# VFD-IV-26-5x7.net
KiCad netlist of a schematic drawn in EAGLE
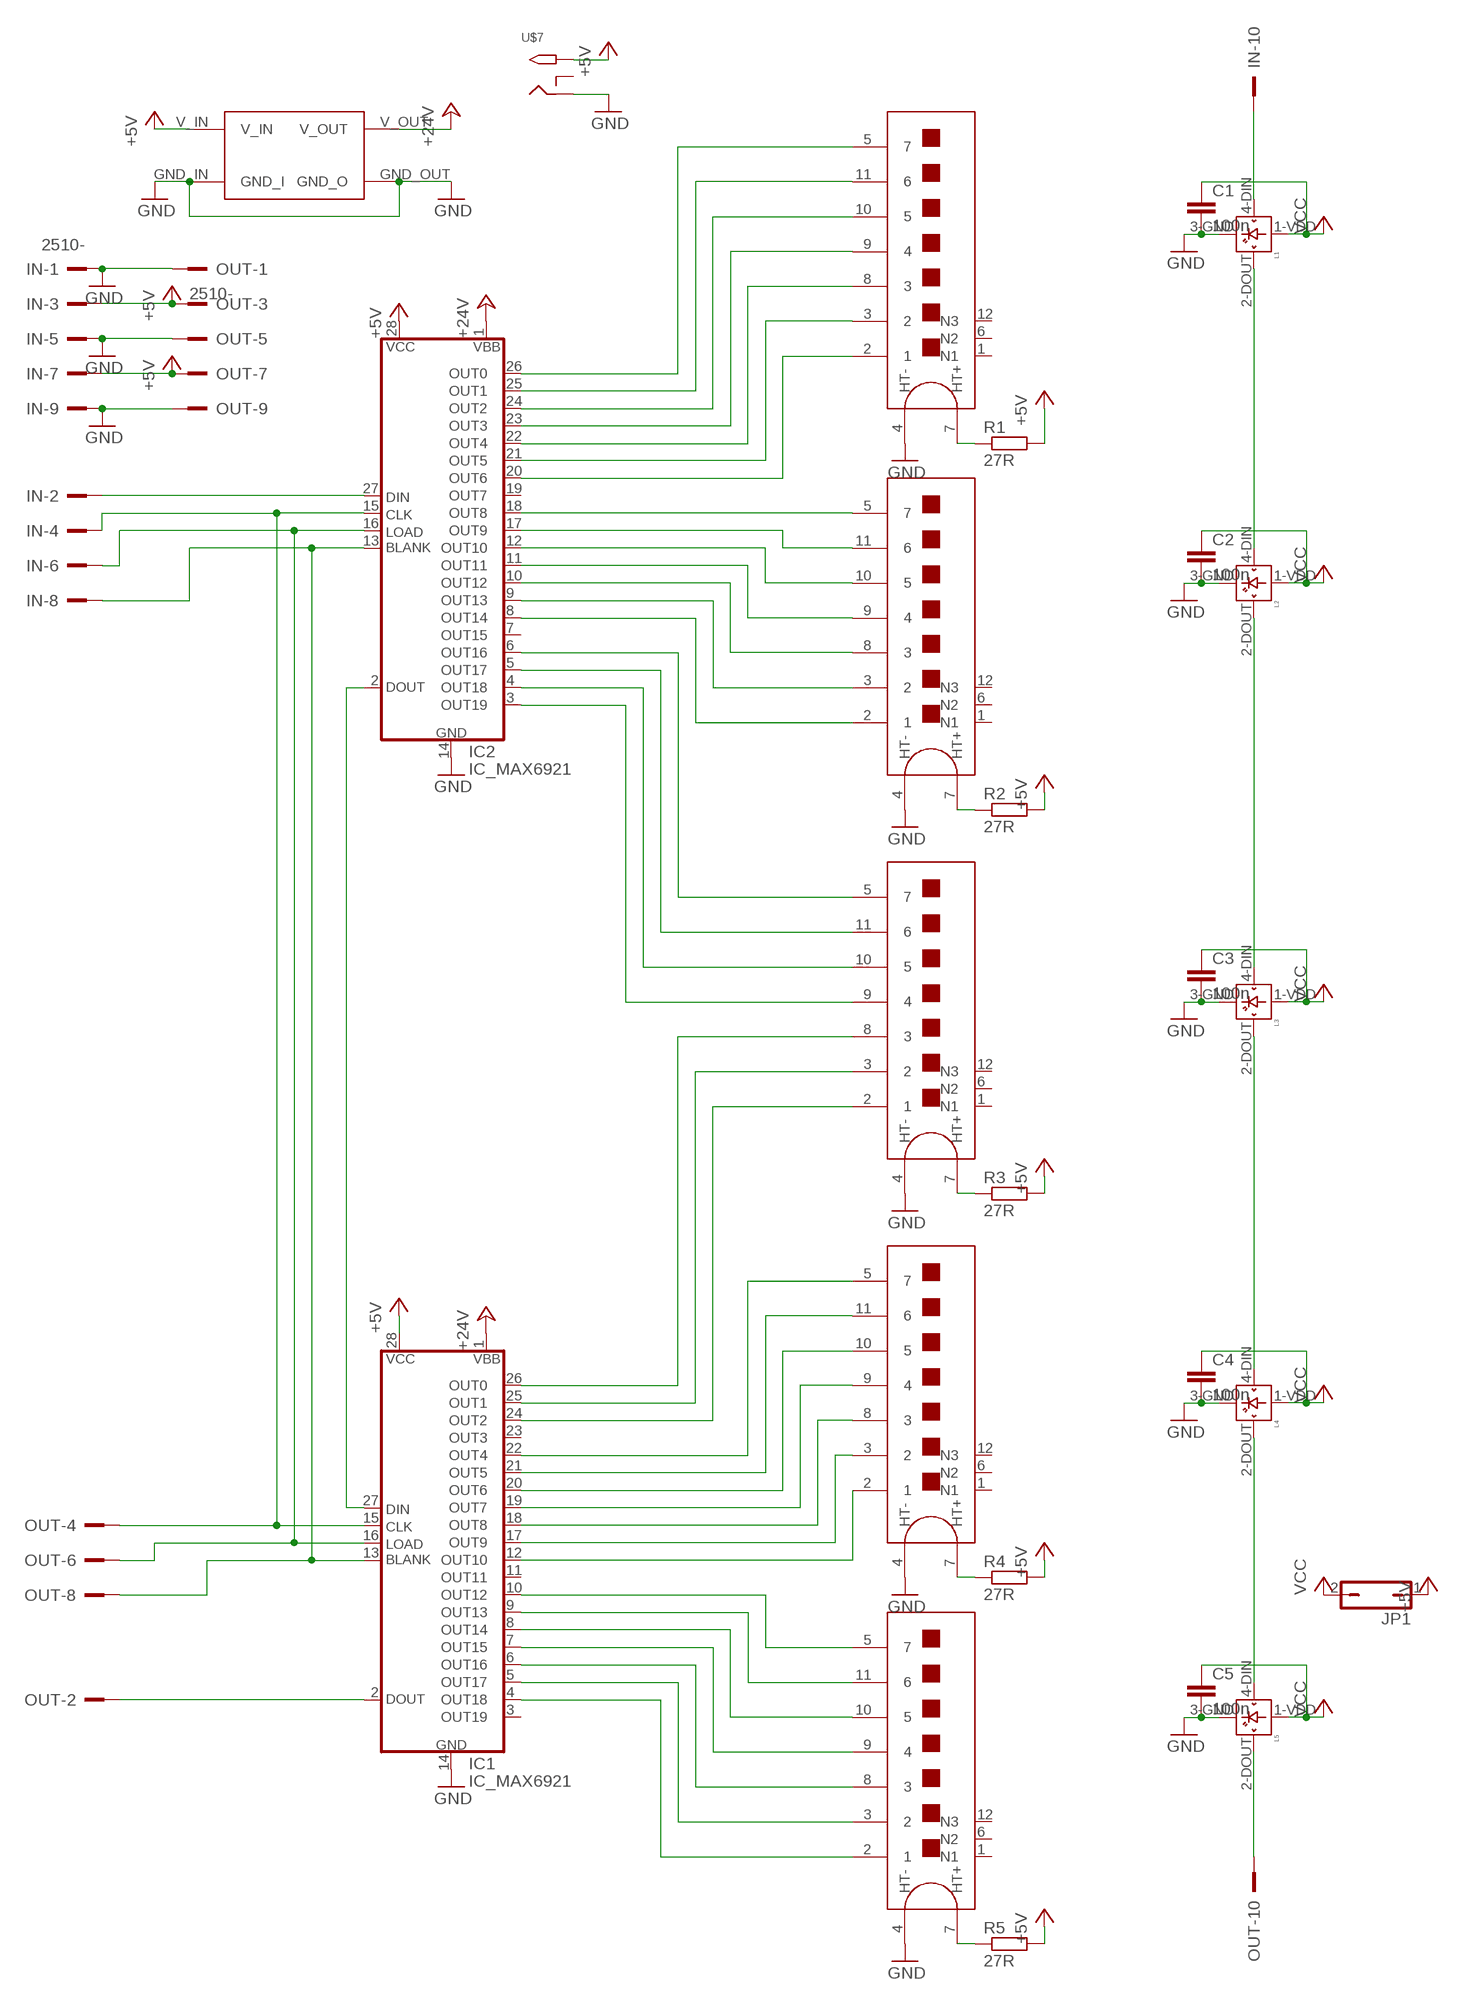
[diagram p0: schematic, sheet 1]

(export (version "E")
  (design (tool "Eeschema 10.0.6"))
  (components
    (comp (ref "1")
      (value "IV-26-T1_DISP")
      (footprint "eagle-import:IV-26")
      (libsource (lib "eagle-import") (part "IV-26-T1_DISP"))
    )
    (comp (ref "2")
      (value "IV-26-T1_DISP")
      (footprint "eagle-import:IV-26")
      (libsource (lib "eagle-import") (part "IV-26-T1_DISP"))
    )
    (comp (ref "3")
      (value "IV-26-T1_DISP")
      (footprint "eagle-import:IV-26")
      (libsource (lib "eagle-import") (part "IV-26-T1_DISP"))
    )
    (comp (ref "4")
      (value "IV-26-T1_DISP")
      (footprint "eagle-import:IV-26")
      (libsource (lib "eagle-import") (part "IV-26-T1_DISP"))
    )
    (comp (ref "5")
      (value "IV-26-T1_DISP")
      (footprint "eagle-import:IV-26")
      (libsource (lib "eagle-import") (part "IV-26-T1_DISP"))
    )
    (comp (ref "C1")
      (value "100n")
      (footprint "eagle-import:C050-025X075")
      (libsource (lib "eagle-import") (part "C-EU050-025X075"))
    )
    (comp (ref "C2")
      (value "100n")
      (footprint "eagle-import:C050-025X075")
      (libsource (lib "eagle-import") (part "C-EU050-025X075"))
    )
    (comp (ref "C3")
      (value "100n")
      (footprint "eagle-import:C050-025X075")
      (libsource (lib "eagle-import") (part "C-EU050-025X075"))
    )
    (comp (ref "C4")
      (value "100n")
      (footprint "eagle-import:C050-025X075")
      (libsource (lib "eagle-import") (part "C-EU050-025X075"))
    )
    (comp (ref "C5")
      (value "100n")
      (footprint "eagle-import:C050-025X075")
      (libsource (lib "eagle-import") (part "C-EU050-025X075"))
    )
    (comp (ref "IC1")
      (value "IC_MAX6921")
      (footprint "eagle-import:S28")
      (libsource (lib "eagle-import") (part "IC_MAX6921"))
    )
    (comp (ref "IC2")
      (value "IC_MAX6921")
      (footprint "eagle-import:S28")
      (libsource (lib "eagle-import") (part "IC_MAX6921"))
    )
    (comp (ref "IN")
      (value "2510-")
      (footprint "eagle-import:PAK100_2500-10")
      (fields (field (name "MF") "3M") (field (name "MPN") "2510-6002UB"))
      (libsource (lib "eagle-import") (part "2510-"))
    )
    (comp (ref "JP1")
      (value "JP1Q")
      (footprint "eagle-import:JP1")
      (libsource (lib "eagle-import") (part "JP1Q"))
    )
    (comp (ref "L1")
      (value "WS2812B")
      (footprint "eagle-import:WS2812B")
      (libsource (lib "eagle-import") (part "WS2812B"))
    )
    (comp (ref "L2")
      (value "WS2812B")
      (footprint "eagle-import:WS2812B")
      (libsource (lib "eagle-import") (part "WS2812B"))
    )
    (comp (ref "L3")
      (value "WS2812B")
      (footprint "eagle-import:WS2812B")
      (libsource (lib "eagle-import") (part "WS2812B"))
    )
    (comp (ref "L4")
      (value "WS2812B")
      (footprint "eagle-import:WS2812B")
      (libsource (lib "eagle-import") (part "WS2812B"))
    )
    (comp (ref "L5")
      (value "WS2812B")
      (footprint "eagle-import:WS2812B")
      (libsource (lib "eagle-import") (part "WS2812B"))
    )
    (comp (ref "OUT")
      (value "2510-")
      (footprint "eagle-import:PAK100_2500-10")
      (fields (field (name "MF") "3M") (field (name "MPN") "2510-6002UB"))
      (libsource (lib "eagle-import") (part "2510-"))
    )
    (comp (ref "R1")
      (value "27R")
      (footprint "eagle-import:0207_10")
      (libsource (lib "eagle-import") (part "R-EU_0207/10"))
    )
    (comp (ref "R2")
      (value "27R")
      (footprint "eagle-import:0207_10")
      (libsource (lib "eagle-import") (part "R-EU_0207/10"))
    )
    (comp (ref "R3")
      (value "27R")
      (footprint "eagle-import:0207_10")
      (libsource (lib "eagle-import") (part "R-EU_0207/10"))
    )
    (comp (ref "R4")
      (value "27R")
      (footprint "eagle-import:0207_10")
      (libsource (lib "eagle-import") (part "R-EU_0207/10"))
    )
    (comp (ref "R5")
      (value "27R")
      (footprint "eagle-import:0207_10")
      (libsource (lib "eagle-import") (part "R-EU_0207/10"))
    )
    (comp (ref "U$6")
      (value "STEP_UP_MODULE")
      (footprint "eagle-import:STEP_UP_MODULE")
      (libsource (lib "eagle-import") (part "STEP_UP_MODULE"))
    )
    (comp (ref "U$7")
      (value "2.1MMJACKTHM")
      (footprint "eagle-import:PJ-102A")
      (libsource (lib "eagle-import") (part "2.1MMJACKTHM"))
    )
  )
  (nets
    (net (code "1") (name "+5V") (class "Default")
      (node (ref "IC1") (pin "28") (pinfunction "VCC_28") (pintype "power_in"))
      (node (ref "IC2") (pin "28") (pinfunction "VCC_28") (pintype "power_in"))
      (node (ref "IN") (pin "3") (pinfunction "KL_3") (pintype "passive"))
      (node (ref "IN") (pin "7") (pinfunction "KL_7") (pintype "passive"))
      (node (ref "JP1") (pin "1") (pinfunction "1_1") (pintype "passive"))
      (node (ref "OUT") (pin "3") (pinfunction "KL_3") (pintype "passive"))
      (node (ref "OUT") (pin "7") (pinfunction "KL_7") (pintype "passive"))
      (node (ref "R1") (pin "2") (pinfunction "2_2") (pintype "passive"))
      (node (ref "R2") (pin "2") (pinfunction "2_2") (pintype "passive"))
      (node (ref "R3") (pin "2") (pinfunction "2_2") (pintype "passive"))
      (node (ref "R4") (pin "2") (pinfunction "2_2") (pintype "passive"))
      (node (ref "R5") (pin "2") (pinfunction "2_2") (pintype "passive"))
      (node (ref "U$6") (pin "V_IN") (pinfunction "V_IN_V_IN") (pintype "power_in"))
      (node (ref "U$7") (pin "TIP") (pinfunction "TIP_TIP") (pintype "bidirectional"))
    )
    (net (code "2") (name "+24V") (class "Default")
      (node (ref "IC1") (pin "1") (pinfunction "VBB_1") (pintype "power_in"))
      (node (ref "IC2") (pin "1") (pinfunction "VBB_1") (pintype "power_in"))
      (node (ref "U$6") (pin "V_OUT") (pinfunction "V_OUT_V_OUT") (pintype "power_in"))
    )
    (net (code "3") (name "GND") (class "Default")
      (node (ref "1") (pin "4") (pinfunction "HT-_4") (pintype "power_in"))
      (node (ref "2") (pin "4") (pinfunction "HT-_4") (pintype "power_in"))
      (node (ref "3") (pin "4") (pinfunction "HT-_4") (pintype "power_in"))
      (node (ref "4") (pin "4") (pinfunction "HT-_4") (pintype "power_in"))
      (node (ref "5") (pin "4") (pinfunction "HT-_4") (pintype "power_in"))
      (node (ref "C1") (pin "2") (pinfunction "2_2") (pintype "passive"))
      (node (ref "C2") (pin "2") (pinfunction "2_2") (pintype "passive"))
      (node (ref "C3") (pin "2") (pinfunction "2_2") (pintype "passive"))
      (node (ref "C4") (pin "2") (pinfunction "2_2") (pintype "passive"))
      (node (ref "C5") (pin "2") (pinfunction "2_2") (pintype "passive"))
      (node (ref "IC1") (pin "14") (pinfunction "GND_14") (pintype "power_in"))
      (node (ref "IC2") (pin "14") (pinfunction "GND_14") (pintype "power_in"))
      (node (ref "IN") (pin "1") (pinfunction "KL_1") (pintype "passive"))
      (node (ref "IN") (pin "5") (pinfunction "KL_5") (pintype "passive"))
      (node (ref "IN") (pin "9") (pinfunction "KL_9") (pintype "passive"))
      (node (ref "L1") (pin "3-GND") (pinfunction "GND_3-GND") (pintype "bidirectional"))
      (node (ref "L2") (pin "3-GND") (pinfunction "GND_3-GND") (pintype "bidirectional"))
      (node (ref "L3") (pin "3-GND") (pinfunction "GND_3-GND") (pintype "bidirectional"))
      (node (ref "L4") (pin "3-GND") (pinfunction "GND_3-GND") (pintype "bidirectional"))
      (node (ref "L5") (pin "3-GND") (pinfunction "GND_3-GND") (pintype "bidirectional"))
      (node (ref "OUT") (pin "1") (pinfunction "KL_1") (pintype "passive"))
      (node (ref "OUT") (pin "5") (pinfunction "KL_5") (pintype "passive"))
      (node (ref "OUT") (pin "9") (pinfunction "KL_9") (pintype "passive"))
      (node (ref "U$6") (pin "GND_IN") (pinfunction "GND_I_GND_IN") (pintype "power_in"))
      (node (ref "U$6") (pin "GND_OUT") (pinfunction "GND_O_GND_OUT") (pintype "power_in"))
      (node (ref "U$7") (pin "RING") (pinfunction "RING_RING") (pintype "bidirectional"))
    )
    (net (code "4") (name "Net-(1-1)") (class "Default")
      (node (ref "1") (pin "2") (pinfunction "1_2") (pintype "input"))
      (node (ref "IC2") (pin "20") (pinfunction "OUT6_20") (pintype "output"))
    )
    (net (code "5") (name "Net-(1-2)") (class "Default")
      (node (ref "1") (pin "3") (pinfunction "2_3") (pintype "input"))
      (node (ref "IC2") (pin "21") (pinfunction "OUT5_21") (pintype "output"))
    )
    (net (code "6") (name "Net-(1-3)") (class "Default")
      (node (ref "1") (pin "8") (pinfunction "3_8") (pintype "input"))
      (node (ref "IC2") (pin "22") (pinfunction "OUT4_22") (pintype "output"))
    )
    (net (code "7") (name "Net-(1-4)") (class "Default")
      (node (ref "1") (pin "9") (pinfunction "4_9") (pintype "input"))
      (node (ref "IC2") (pin "23") (pinfunction "OUT3_23") (pintype "output"))
    )
    (net (code "8") (name "Net-(1-5)") (class "Default")
      (node (ref "1") (pin "10") (pinfunction "5_10") (pintype "input"))
      (node (ref "IC2") (pin "24") (pinfunction "OUT2_24") (pintype "output"))
    )
    (net (code "9") (name "Net-(1-6)") (class "Default")
      (node (ref "1") (pin "11") (pinfunction "6_11") (pintype "input"))
      (node (ref "IC2") (pin "25") (pinfunction "OUT1_25") (pintype "output"))
    )
    (net (code "10") (name "Net-(1-7)") (class "Default")
      (node (ref "1") (pin "5") (pinfunction "7_5") (pintype "input"))
      (node (ref "IC2") (pin "26") (pinfunction "OUT0_26") (pintype "output"))
    )
    (net (code "11") (name "Net-(1-HT+)") (class "Default")
      (node (ref "1") (pin "7") (pinfunction "HT+_7") (pintype "power_in"))
      (node (ref "R1") (pin "1") (pinfunction "1_1") (pintype "passive"))
    )
    (net (code "12") (name "Net-(2-1)") (class "Default")
      (node (ref "2") (pin "2") (pinfunction "1_2") (pintype "input"))
      (node (ref "IC2") (pin "8") (pinfunction "OUT14_8") (pintype "output"))
    )
    (net (code "13") (name "Net-(2-2)") (class "Default")
      (node (ref "2") (pin "3") (pinfunction "2_3") (pintype "input"))
      (node (ref "IC2") (pin "9") (pinfunction "OUT13_9") (pintype "output"))
    )
    (net (code "14") (name "Net-(2-3)") (class "Default")
      (node (ref "2") (pin "8") (pinfunction "3_8") (pintype "input"))
      (node (ref "IC2") (pin "10") (pinfunction "OUT12_10") (pintype "output"))
    )
    (net (code "15") (name "Net-(2-4)") (class "Default")
      (node (ref "2") (pin "9") (pinfunction "4_9") (pintype "input"))
      (node (ref "IC2") (pin "11") (pinfunction "OUT11_11") (pintype "output"))
    )
    (net (code "16") (name "Net-(2-5)") (class "Default")
      (node (ref "2") (pin "10") (pinfunction "5_10") (pintype "input"))
      (node (ref "IC2") (pin "12") (pinfunction "OUT10_12") (pintype "output"))
    )
    (net (code "17") (name "Net-(2-6)") (class "Default")
      (node (ref "2") (pin "11") (pinfunction "6_11") (pintype "input"))
      (node (ref "IC2") (pin "17") (pinfunction "OUT9_17") (pintype "output"))
    )
    (net (code "18") (name "Net-(2-7)") (class "Default")
      (node (ref "2") (pin "5") (pinfunction "7_5") (pintype "input"))
      (node (ref "IC2") (pin "18") (pinfunction "OUT8_18") (pintype "output"))
    )
    (net (code "19") (name "Net-(2-HT+)") (class "Default")
      (node (ref "2") (pin "7") (pinfunction "HT+_7") (pintype "power_in"))
      (node (ref "R2") (pin "1") (pinfunction "1_1") (pintype "passive"))
    )
    (net (code "20") (name "Net-(3-1)") (class "Default")
      (node (ref "3") (pin "2") (pinfunction "1_2") (pintype "input"))
      (node (ref "IC1") (pin "24") (pinfunction "OUT2_24") (pintype "output"))
    )
    (net (code "21") (name "Net-(3-2)") (class "Default")
      (node (ref "3") (pin "3") (pinfunction "2_3") (pintype "input"))
      (node (ref "IC1") (pin "25") (pinfunction "OUT1_25") (pintype "output"))
    )
    (net (code "22") (name "Net-(3-3)") (class "Default")
      (node (ref "3") (pin "8") (pinfunction "3_8") (pintype "input"))
      (node (ref "IC1") (pin "26") (pinfunction "OUT0_26") (pintype "output"))
    )
    (net (code "23") (name "Net-(3-4)") (class "Default")
      (node (ref "3") (pin "9") (pinfunction "4_9") (pintype "input"))
      (node (ref "IC2") (pin "3") (pinfunction "OUT19_3") (pintype "output"))
    )
    (net (code "24") (name "Net-(3-5)") (class "Default")
      (node (ref "3") (pin "10") (pinfunction "5_10") (pintype "input"))
      (node (ref "IC2") (pin "4") (pinfunction "OUT18_4") (pintype "output"))
    )
    (net (code "25") (name "Net-(3-6)") (class "Default")
      (node (ref "3") (pin "11") (pinfunction "6_11") (pintype "input"))
      (node (ref "IC2") (pin "5") (pinfunction "OUT17_5") (pintype "output"))
    )
    (net (code "26") (name "Net-(3-7)") (class "Default")
      (node (ref "3") (pin "5") (pinfunction "7_5") (pintype "input"))
      (node (ref "IC2") (pin "6") (pinfunction "OUT16_6") (pintype "output"))
    )
    (net (code "27") (name "Net-(3-HT+)") (class "Default")
      (node (ref "3") (pin "7") (pinfunction "HT+_7") (pintype "power_in"))
      (node (ref "R3") (pin "1") (pinfunction "1_1") (pintype "passive"))
    )
    (net (code "28") (name "Net-(4-1)") (class "Default")
      (node (ref "4") (pin "2") (pinfunction "1_2") (pintype "input"))
      (node (ref "IC1") (pin "12") (pinfunction "OUT10_12") (pintype "output"))
    )
    (net (code "29") (name "Net-(4-2)") (class "Default")
      (node (ref "4") (pin "3") (pinfunction "2_3") (pintype "input"))
      (node (ref "IC1") (pin "17") (pinfunction "OUT9_17") (pintype "output"))
    )
    (net (code "30") (name "Net-(4-3)") (class "Default")
      (node (ref "4") (pin "8") (pinfunction "3_8") (pintype "input"))
      (node (ref "IC1") (pin "18") (pinfunction "OUT8_18") (pintype "output"))
    )
    (net (code "31") (name "Net-(4-4)") (class "Default")
      (node (ref "4") (pin "9") (pinfunction "4_9") (pintype "input"))
      (node (ref "IC1") (pin "19") (pinfunction "OUT7_19") (pintype "output"))
    )
    (net (code "32") (name "Net-(4-5)") (class "Default")
      (node (ref "4") (pin "10") (pinfunction "5_10") (pintype "input"))
      (node (ref "IC1") (pin "20") (pinfunction "OUT6_20") (pintype "output"))
    )
    (net (code "33") (name "Net-(4-6)") (class "Default")
      (node (ref "4") (pin "11") (pinfunction "6_11") (pintype "input"))
      (node (ref "IC1") (pin "21") (pinfunction "OUT5_21") (pintype "output"))
    )
    (net (code "34") (name "Net-(4-7)") (class "Default")
      (node (ref "4") (pin "5") (pinfunction "7_5") (pintype "input"))
      (node (ref "IC1") (pin "22") (pinfunction "OUT4_22") (pintype "output"))
    )
    (net (code "35") (name "Net-(4-HT+)") (class "Default")
      (node (ref "4") (pin "7") (pinfunction "HT+_7") (pintype "power_in"))
      (node (ref "R4") (pin "1") (pinfunction "1_1") (pintype "passive"))
    )
    (net (code "36") (name "Net-(5-1)") (class "Default")
      (node (ref "5") (pin "2") (pinfunction "1_2") (pintype "input"))
      (node (ref "IC1") (pin "4") (pinfunction "OUT18_4") (pintype "output"))
    )
    (net (code "37") (name "Net-(5-2)") (class "Default")
      (node (ref "5") (pin "3") (pinfunction "2_3") (pintype "input"))
      (node (ref "IC1") (pin "5") (pinfunction "OUT17_5") (pintype "output"))
    )
    (net (code "38") (name "Net-(5-3)") (class "Default")
      (node (ref "5") (pin "8") (pinfunction "3_8") (pintype "input"))
      (node (ref "IC1") (pin "6") (pinfunction "OUT16_6") (pintype "output"))
    )
    (net (code "39") (name "Net-(5-4)") (class "Default")
      (node (ref "5") (pin "9") (pinfunction "4_9") (pintype "input"))
      (node (ref "IC1") (pin "7") (pinfunction "OUT15_7") (pintype "output"))
    )
    (net (code "40") (name "Net-(5-5)") (class "Default")
      (node (ref "5") (pin "10") (pinfunction "5_10") (pintype "input"))
      (node (ref "IC1") (pin "8") (pinfunction "OUT14_8") (pintype "output"))
    )
    (net (code "41") (name "Net-(5-6)") (class "Default")
      (node (ref "5") (pin "11") (pinfunction "6_11") (pintype "input"))
      (node (ref "IC1") (pin "9") (pinfunction "OUT13_9") (pintype "output"))
    )
    (net (code "42") (name "Net-(5-7)") (class "Default")
      (node (ref "5") (pin "5") (pinfunction "7_5") (pintype "input"))
      (node (ref "IC1") (pin "10") (pinfunction "OUT12_10") (pintype "output"))
    )
    (net (code "43") (name "Net-(5-HT+)") (class "Default")
      (node (ref "5") (pin "7") (pinfunction "HT+_7") (pintype "power_in"))
      (node (ref "R5") (pin "1") (pinfunction "1_1") (pintype "passive"))
    )
    (net (code "44") (name "Net-(IC1-BLANK)") (class "Default")
      (node (ref "IC1") (pin "13") (pinfunction "BLANK_13") (pintype "input"))
      (node (ref "IC2") (pin "13") (pinfunction "BLANK_13") (pintype "input"))
      (node (ref "IN") (pin "8") (pinfunction "KL_8") (pintype "passive"))
      (node (ref "OUT") (pin "8") (pinfunction "KL_8") (pintype "passive"))
    )
    (net (code "45") (name "Net-(IC1-CLK)") (class "Default")
      (node (ref "IC1") (pin "15") (pinfunction "CLK_15") (pintype "input"))
      (node (ref "IC2") (pin "15") (pinfunction "CLK_15") (pintype "input"))
      (node (ref "IN") (pin "4") (pinfunction "KL_4") (pintype "passive"))
      (node (ref "OUT") (pin "4") (pinfunction "KL_4") (pintype "passive"))
    )
    (net (code "46") (name "Net-(IC1-DIN)") (class "Default")
      (node (ref "IC1") (pin "27") (pinfunction "DIN_27") (pintype "input"))
      (node (ref "IC2") (pin "2") (pinfunction "DOUT_2") (pintype "output"))
    )
    (net (code "47") (name "Net-(IC1-DOUT)") (class "Default")
      (node (ref "IC1") (pin "2") (pinfunction "DOUT_2") (pintype "output"))
      (node (ref "OUT") (pin "2") (pinfunction "KL_2") (pintype "passive"))
    )
    (net (code "48") (name "Net-(IC1-LOAD)") (class "Default")
      (node (ref "IC1") (pin "16") (pinfunction "LOAD_16") (pintype "input"))
      (node (ref "IC2") (pin "16") (pinfunction "LOAD_16") (pintype "input"))
      (node (ref "IN") (pin "6") (pinfunction "KL_6") (pintype "passive"))
      (node (ref "OUT") (pin "6") (pinfunction "KL_6") (pintype "passive"))
    )
    (net (code "49") (name "Net-(IC2-DIN)") (class "Default")
      (node (ref "IC2") (pin "27") (pinfunction "DIN_27") (pintype "input"))
      (node (ref "IN") (pin "2") (pinfunction "KL_2") (pintype "passive"))
    )
    (net (code "50") (name "Net-(INB-KL)") (class "Default")
      (node (ref "IN") (pin "10") (pinfunction "KL_10") (pintype "passive"))
      (node (ref "L1") (pin "4-DIN") (pinfunction "DIN_4-DIN") (pintype "input"))
    )
    (net (code "51") (name "Net-(L1-DOUT)") (class "Default")
      (node (ref "L1") (pin "2-DOUT") (pinfunction "DOUT_2-DOUT") (pintype "output"))
      (node (ref "L2") (pin "4-DIN") (pinfunction "DIN_4-DIN") (pintype "input"))
    )
    (net (code "52") (name "Net-(L2-DOUT)") (class "Default")
      (node (ref "L2") (pin "2-DOUT") (pinfunction "DOUT_2-DOUT") (pintype "output"))
      (node (ref "L3") (pin "4-DIN") (pinfunction "DIN_4-DIN") (pintype "input"))
    )
    (net (code "53") (name "Net-(L3-DOUT)") (class "Default")
      (node (ref "L3") (pin "2-DOUT") (pinfunction "DOUT_2-DOUT") (pintype "output"))
      (node (ref "L4") (pin "4-DIN") (pinfunction "DIN_4-DIN") (pintype "input"))
    )
    (net (code "54") (name "Net-(L4-DOUT)") (class "Default")
      (node (ref "L4") (pin "2-DOUT") (pinfunction "DOUT_2-DOUT") (pintype "output"))
      (node (ref "L5") (pin "4-DIN") (pinfunction "DIN_4-DIN") (pintype "input"))
    )
    (net (code "55") (name "Net-(L5-DOUT)") (class "Default")
      (node (ref "L5") (pin "2-DOUT") (pinfunction "DOUT_2-DOUT") (pintype "output"))
      (node (ref "OUT") (pin "10") (pinfunction "KL_10") (pintype "passive"))
    )
    (net (code "56") (name "VCC") (class "Default")
      (node (ref "C1") (pin "1") (pinfunction "1_1") (pintype "passive"))
      (node (ref "C2") (pin "1") (pinfunction "1_1") (pintype "passive"))
      (node (ref "C3") (pin "1") (pinfunction "1_1") (pintype "passive"))
      (node (ref "C4") (pin "1") (pinfunction "1_1") (pintype "passive"))
      (node (ref "C5") (pin "1") (pinfunction "1_1") (pintype "passive"))
      (node (ref "JP1") (pin "2") (pinfunction "2_2") (pintype "passive"))
      (node (ref "L1") (pin "1-VDD") (pinfunction "VDD_1-VDD") (pintype "bidirectional"))
      (node (ref "L2") (pin "1-VDD") (pinfunction "VDD_1-VDD") (pintype "bidirectional"))
      (node (ref "L3") (pin "1-VDD") (pinfunction "VDD_1-VDD") (pintype "bidirectional"))
      (node (ref "L4") (pin "1-VDD") (pinfunction "VDD_1-VDD") (pintype "bidirectional"))
      (node (ref "L5") (pin "1-VDD") (pinfunction "VDD_1-VDD") (pintype "bidirectional"))
    )
    (net (code "57") (name "unconnected-(1-N1-Pad1)") (class "Default")
      (node (ref "1") (pin "1") (pinfunction "N1_1") (pintype "no_connect"))
    )
    (net (code "58") (name "unconnected-(1-N2-Pad6)") (class "Default")
      (node (ref "1") (pin "6") (pinfunction "N2_6") (pintype "no_connect"))
    )
    (net (code "59") (name "unconnected-(1-N3-Pad12)") (class "Default")
      (node (ref "1") (pin "12") (pinfunction "N3_12") (pintype "no_connect"))
    )
    (net (code "60") (name "unconnected-(2-N1-Pad1)") (class "Default")
      (node (ref "2") (pin "1") (pinfunction "N1_1") (pintype "no_connect"))
    )
    (net (code "61") (name "unconnected-(2-N2-Pad6)") (class "Default")
      (node (ref "2") (pin "6") (pinfunction "N2_6") (pintype "no_connect"))
    )
    (net (code "62") (name "unconnected-(2-N3-Pad12)") (class "Default")
      (node (ref "2") (pin "12") (pinfunction "N3_12") (pintype "no_connect"))
    )
    (net (code "63") (name "unconnected-(3-N1-Pad1)") (class "Default")
      (node (ref "3") (pin "1") (pinfunction "N1_1") (pintype "no_connect"))
    )
    (net (code "64") (name "unconnected-(3-N2-Pad6)") (class "Default")
      (node (ref "3") (pin "6") (pinfunction "N2_6") (pintype "no_connect"))
    )
    (net (code "65") (name "unconnected-(3-N3-Pad12)") (class "Default")
      (node (ref "3") (pin "12") (pinfunction "N3_12") (pintype "no_connect"))
    )
    (net (code "66") (name "unconnected-(4-N1-Pad1)") (class "Default")
      (node (ref "4") (pin "1") (pinfunction "N1_1") (pintype "no_connect"))
    )
    (net (code "67") (name "unconnected-(4-N2-Pad6)") (class "Default")
      (node (ref "4") (pin "6") (pinfunction "N2_6") (pintype "no_connect"))
    )
    (net (code "68") (name "unconnected-(4-N3-Pad12)") (class "Default")
      (node (ref "4") (pin "12") (pinfunction "N3_12") (pintype "no_connect"))
    )
    (net (code "69") (name "unconnected-(5-N1-Pad1)") (class "Default")
      (node (ref "5") (pin "1") (pinfunction "N1_1") (pintype "no_connect"))
    )
    (net (code "70") (name "unconnected-(5-N2-Pad6)") (class "Default")
      (node (ref "5") (pin "6") (pinfunction "N2_6") (pintype "no_connect"))
    )
    (net (code "71") (name "unconnected-(5-N3-Pad12)") (class "Default")
      (node (ref "5") (pin "12") (pinfunction "N3_12") (pintype "no_connect"))
    )
    (net (code "72") (name "unconnected-(IC1-OUT3-Pad23)") (class "Default")
      (node (ref "IC1") (pin "23") (pinfunction "OUT3_23") (pintype "output"))
    )
    (net (code "73") (name "unconnected-(IC1-OUT11-Pad11)") (class "Default")
      (node (ref "IC1") (pin "11") (pinfunction "OUT11_11") (pintype "output"))
    )
    (net (code "74") (name "unconnected-(IC1-OUT19-Pad3)") (class "Default")
      (node (ref "IC1") (pin "3") (pinfunction "OUT19_3") (pintype "output"))
    )
    (net (code "75") (name "unconnected-(IC2-OUT7-Pad19)") (class "Default")
      (node (ref "IC2") (pin "19") (pinfunction "OUT7_19") (pintype "output"))
    )
    (net (code "76") (name "unconnected-(IC2-OUT15-Pad7)") (class "Default")
      (node (ref "IC2") (pin "7") (pinfunction "OUT15_7") (pintype "output"))
    )
    (net (code "77") (name "unconnected-(U$7-PadRING_SW)") (class "Default")
      (node (ref "U$7") (pin "RING_SW") (pinfunction "RING_SW_RING_SW") (pintype "bidirectional"))
    )
  )
)
